# ComponentCounterLeds-2.net
KiCad netlist of a schematic drawn in EAGLE
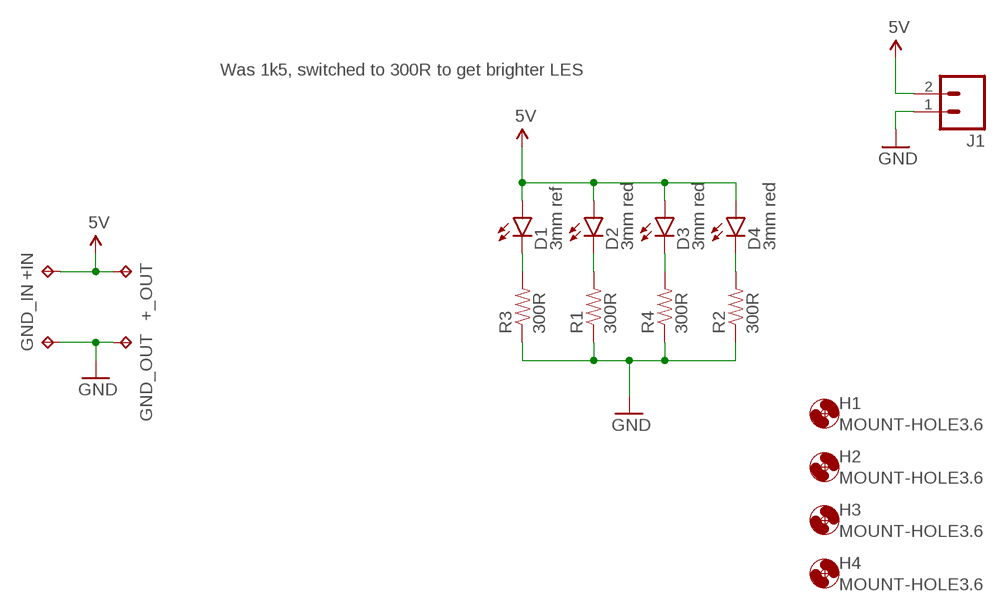
[diagram p0: schematic, sheet 1]

(export (version "E")
  (design (tool "Eeschema 10.0.6"))
  (components
    (comp (ref "+IN")
      (value "TPTP15R")
      (footprint "eagle-import:TP15R")
      (libsource (lib "eagle-import") (part "TPTP15R"))
    )
    (comp (ref "+_OUT")
      (value "TPTP15R")
      (footprint "eagle-import:TP15R")
      (libsource (lib "eagle-import") (part "TPTP15R"))
    )
    (comp (ref "D1")
      (value "3mm ref")
      (footprint "eagle-import:LED3MM-NS")
      (libsource (lib "eagle-import") (part "LED-3MM-NO_SILK"))
    )
    (comp (ref "D2")
      (value "3mm red")
      (footprint "eagle-import:LED3MM-NS")
      (libsource (lib "eagle-import") (part "LED-3MM-NO_SILK"))
    )
    (comp (ref "D3")
      (value "3mm red")
      (footprint "eagle-import:LED3MM-NS")
      (libsource (lib "eagle-import") (part "LED-3MM-NO_SILK"))
    )
    (comp (ref "D4")
      (value "3mm red")
      (footprint "eagle-import:LED3MM-NS")
      (libsource (lib "eagle-import") (part "LED-3MM-NO_SILK"))
    )
    (comp (ref "GND_IN")
      (value "TPTP15R")
      (footprint "eagle-import:TP15R")
      (libsource (lib "eagle-import") (part "TPTP15R"))
    )
    (comp (ref "GND_OUT")
      (value "TPTP15R")
      (footprint "eagle-import:TP15R")
      (libsource (lib "eagle-import") (part "TPTP15R"))
    )
    (comp (ref "H1")
      (value "MOUNT-HOLE3.6")
      (footprint "eagle-import:3,6")
      (libsource (lib "eagle-import") (part "MOUNT-HOLE3.6"))
    )
    (comp (ref "H2")
      (value "MOUNT-HOLE3.6")
      (footprint "eagle-import:3,6")
      (libsource (lib "eagle-import") (part "MOUNT-HOLE3.6"))
    )
    (comp (ref "H3")
      (value "MOUNT-HOLE3.6")
      (footprint "eagle-import:3,6")
      (libsource (lib "eagle-import") (part "MOUNT-HOLE3.6"))
    )
    (comp (ref "H4")
      (value "MOUNT-HOLE3.6")
      (footprint "eagle-import:3,6")
      (libsource (lib "eagle-import") (part "MOUNT-HOLE3.6"))
    )
    (comp (ref "J1")
      (value "M02-JST-2MM-SMT")
      (footprint "eagle-import:JST-2-SMD")
      (libsource (lib "eagle-import") (part "M02-JST-2MM-SMT"))
    )
    (comp (ref "R1")
      (value "300R")
      (footprint "eagle-import:1206")
      (libsource (lib "eagle-import") (part "RESISTOR1206"))
    )
    (comp (ref "R2")
      (value "300R")
      (footprint "eagle-import:1206")
      (libsource (lib "eagle-import") (part "RESISTOR1206"))
    )
    (comp (ref "R3")
      (value "300R")
      (footprint "eagle-import:1206")
      (libsource (lib "eagle-import") (part "RESISTOR1206"))
    )
    (comp (ref "R4")
      (value "300R")
      (footprint "eagle-import:1206")
      (libsource (lib "eagle-import") (part "RESISTOR1206"))
    )
  )
  (nets
    (net (code "1") (name "5V") (class "Default")
      (node (ref "+IN") (pin "TP") (pinfunction "TP_TP") (pintype "input"))
      (node (ref "+_OUT") (pin "TP") (pinfunction "TP_TP") (pintype "input"))
      (node (ref "D1") (pin "A") (pinfunction "A_A") (pintype "passive"))
      (node (ref "D2") (pin "A") (pinfunction "A_A") (pintype "passive"))
      (node (ref "D3") (pin "A") (pinfunction "A_A") (pintype "passive"))
      (node (ref "D4") (pin "A") (pinfunction "A_A") (pintype "passive"))
      (node (ref "J1") (pin "2") (pinfunction "1_2") (pintype "passive"))
    )
    (net (code "2") (name "GND") (class "Default")
      (node (ref "GND_IN") (pin "TP") (pinfunction "TP_TP") (pintype "input"))
      (node (ref "GND_OUT") (pin "TP") (pinfunction "TP_TP") (pintype "input"))
      (node (ref "J1") (pin "1") (pinfunction "2_1") (pintype "passive"))
      (node (ref "R1") (pin "1") (pinfunction "1_1") (pintype "passive"))
      (node (ref "R2") (pin "1") (pinfunction "1_1") (pintype "passive"))
      (node (ref "R3") (pin "1") (pinfunction "1_1") (pintype "passive"))
      (node (ref "R4") (pin "1") (pinfunction "1_1") (pintype "passive"))
    )
    (net (code "3") (name "Net-(D1-C)") (class "Default")
      (node (ref "D1") (pin "K") (pinfunction "C_K") (pintype "passive"))
      (node (ref "R3") (pin "2") (pinfunction "2_2") (pintype "passive"))
    )
    (net (code "4") (name "Net-(D2-C)") (class "Default")
      (node (ref "D2") (pin "K") (pinfunction "C_K") (pintype "passive"))
      (node (ref "R1") (pin "2") (pinfunction "2_2") (pintype "passive"))
    )
    (net (code "5") (name "Net-(D3-C)") (class "Default")
      (node (ref "D3") (pin "K") (pinfunction "C_K") (pintype "passive"))
      (node (ref "R4") (pin "2") (pinfunction "2_2") (pintype "passive"))
    )
    (net (code "6") (name "Net-(D4-C)") (class "Default")
      (node (ref "D4") (pin "K") (pinfunction "C_K") (pintype "passive"))
      (node (ref "R2") (pin "2") (pinfunction "2_2") (pintype "passive"))
    )
  )
)
